# RPi-FabScan-HAT_v11.net
KiCad netlist of a schematic drawn in EAGLE
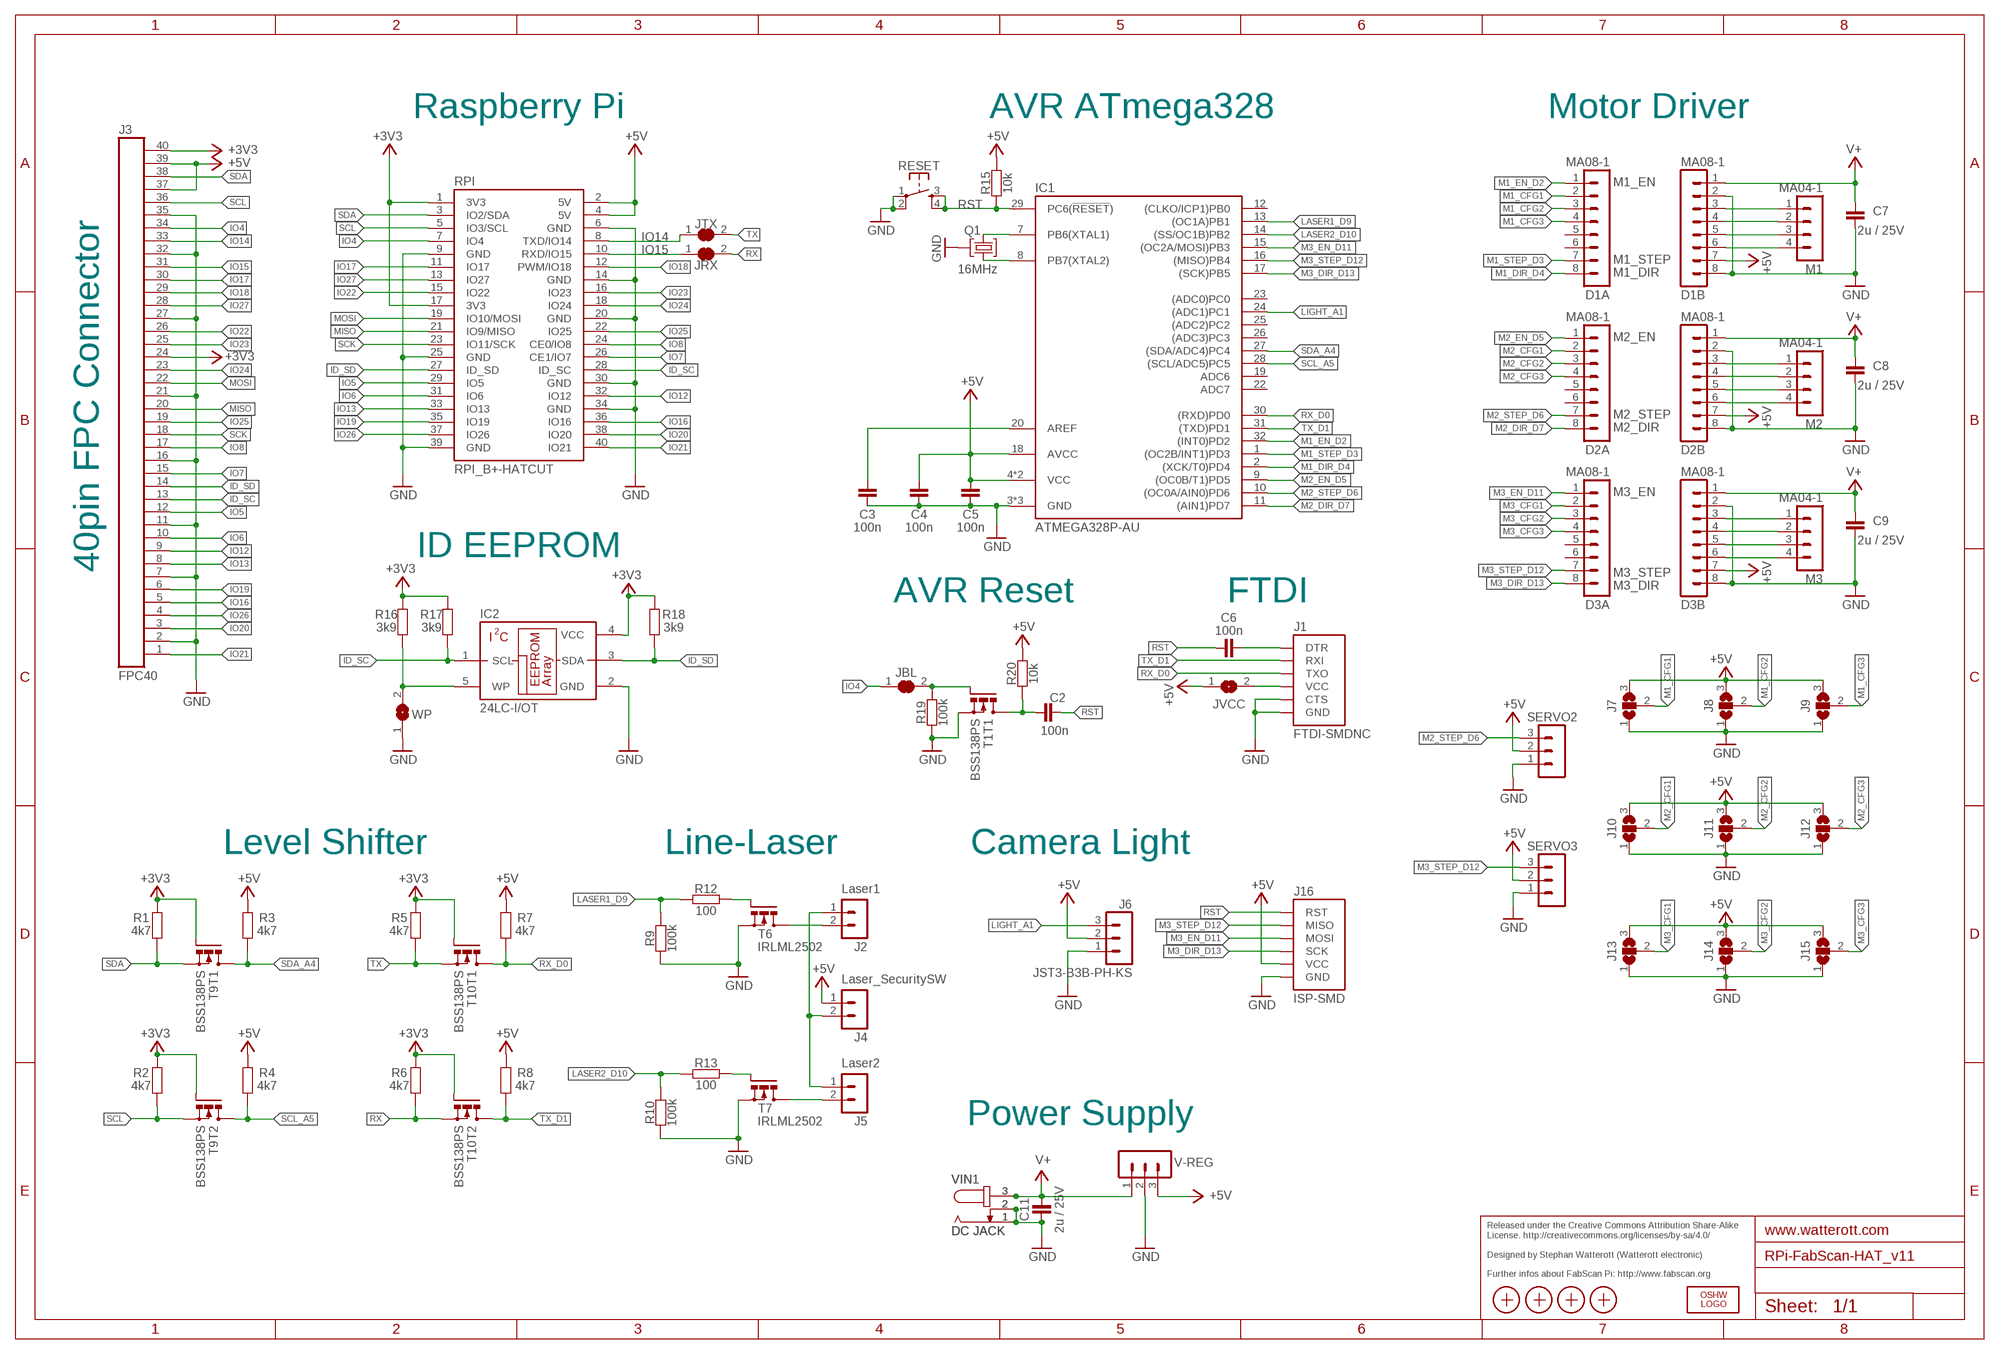
[diagram p0: schematic, sheet 1]

(export (version "E")
  (design (tool "Eeschema 10.0.6"))
  (components
    (comp (ref "1")
      (value "PASSER-07")
      (footprint "eagle-import:PASSER_07MM")
      (libsource (lib "eagle-import") (part "PASSER-07"))
    )
    (comp (ref "2")
      (value "PASSER-07")
      (footprint "eagle-import:PASSER_07MM")
      (libsource (lib "eagle-import") (part "PASSER-07"))
    )
    (comp (ref "C2")
      (value "100n")
      (footprint "eagle-import:C0402")
      (libsource (lib "eagle-import") (part "CAPACITOR-0402"))
    )
    (comp (ref "C3")
      (value "100n")
      (footprint "eagle-import:C0402")
      (libsource (lib "eagle-import") (part "CAPACITOR-0402"))
    )
    (comp (ref "C4")
      (value "100n")
      (footprint "eagle-import:C0402")
      (libsource (lib "eagle-import") (part "CAPACITOR-0402"))
    )
    (comp (ref "C5")
      (value "100n")
      (footprint "eagle-import:C0402")
      (libsource (lib "eagle-import") (part "CAPACITOR-0402"))
    )
    (comp (ref "C6")
      (value "100n")
      (footprint "eagle-import:C0402")
      (libsource (lib "eagle-import") (part "CAPACITOR-0402"))
    )
    (comp (ref "C7")
      (value "2u / 25V")
      (footprint "eagle-import:C1206")
      (libsource (lib "eagle-import") (part "CAPACITOR-1206"))
    )
    (comp (ref "C8")
      (value "2u / 25V")
      (footprint "eagle-import:C1206")
      (libsource (lib "eagle-import") (part "CAPACITOR-1206"))
    )
    (comp (ref "C9")
      (value "2u / 25V")
      (footprint "eagle-import:C1206")
      (libsource (lib "eagle-import") (part "CAPACITOR-1206"))
    )
    (comp (ref "C11")
      (value "2u / 25V")
      (footprint "eagle-import:C1206")
      (libsource (lib "eagle-import") (part "CAPACITOR-1206"))
    )
    (comp (ref "D1A")
      (value "MA08-1")
      (footprint "eagle-import:MA08-1")
      (libsource (lib "eagle-import") (part "MA08-1"))
    )
    (comp (ref "D1B")
      (value "MA08-1")
      (footprint "eagle-import:MA08-1")
      (libsource (lib "eagle-import") (part "MA08-1"))
    )
    (comp (ref "D2A")
      (value "MA08-1")
      (footprint "eagle-import:MA08-1")
      (libsource (lib "eagle-import") (part "MA08-1"))
    )
    (comp (ref "D2B")
      (value "MA08-1")
      (footprint "eagle-import:MA08-1")
      (libsource (lib "eagle-import") (part "MA08-1"))
    )
    (comp (ref "D3A")
      (value "MA08-1")
      (footprint "eagle-import:MA08-1")
      (libsource (lib "eagle-import") (part "MA08-1"))
    )
    (comp (ref "D3B")
      (value "MA08-1")
      (footprint "eagle-import:MA08-1")
      (libsource (lib "eagle-import") (part "MA08-1"))
    )
    (comp (ref "IC1")
      (value "ATMEGA328P-AU")
      (footprint "eagle-import:TQFP32")
      (libsource (lib "eagle-import") (part "ATMEGA328P-AU"))
    )
    (comp (ref "IC2")
      (value "24LC-I/OT")
      (footprint "eagle-import:SOT23-5")
      (libsource (lib "eagle-import") (part "24LC-I/OT"))
    )
    (comp (ref "J1")
      (value "FTDI-SMDNC")
      (footprint "eagle-import:FTDI_SMDNC")
      (libsource (lib "eagle-import") (part "FTDI-SMDNC"))
    )
    (comp (ref "J2")
      (value "Laser1")
      (footprint "eagle-import:MA02-1")
      (libsource (lib "eagle-import") (part "MA02-1"))
    )
    (comp (ref "J3")
      (value "FPC40")
      (footprint "eagle-import:FPC40-0.5")
      (libsource (lib "eagle-import") (part "FPC40"))
    )
    (comp (ref "J4")
      (value "Laser_SecuritySW")
      (footprint "eagle-import:MA02-1")
      (libsource (lib "eagle-import") (part "MA02-1"))
    )
    (comp (ref "J5")
      (value "Laser2")
      (footprint "eagle-import:MA02-1")
      (libsource (lib "eagle-import") (part "MA02-1"))
    )
    (comp (ref "J6")
      (value "JST3-B3B-PH-KS")
      (footprint "eagle-import:JST_B3B-PH-KS")
      (libsource (lib "eagle-import") (part "JST3-B3B-PH-KS"))
    )
    (comp (ref "J7")
      (value "JUMPER3-0603-NC")
      (footprint "eagle-import:JUMPER3-0603_NC")
      (libsource (lib "eagle-import") (part "JUMPER3-0603-NC"))
    )
    (comp (ref "J8")
      (value "JUMPER3-0603-NC")
      (footprint "eagle-import:JUMPER3-0603_NC")
      (libsource (lib "eagle-import") (part "JUMPER3-0603-NC"))
    )
    (comp (ref "J9")
      (value "JUMPER3-0603-NC")
      (footprint "eagle-import:JUMPER3-0603_NC")
      (libsource (lib "eagle-import") (part "JUMPER3-0603-NC"))
    )
    (comp (ref "J10")
      (value "JUMPER3-0603-NC")
      (footprint "eagle-import:JUMPER3-0603_NC")
      (libsource (lib "eagle-import") (part "JUMPER3-0603-NC"))
    )
    (comp (ref "J11")
      (value "JUMPER3-0603-NC")
      (footprint "eagle-import:JUMPER3-0603_NC")
      (libsource (lib "eagle-import") (part "JUMPER3-0603-NC"))
    )
    (comp (ref "J12")
      (value "JUMPER3-0603-NC")
      (footprint "eagle-import:JUMPER3-0603_NC")
      (libsource (lib "eagle-import") (part "JUMPER3-0603-NC"))
    )
    (comp (ref "J13")
      (value "JUMPER3-0603-NC")
      (footprint "eagle-import:JUMPER3-0603_NC")
      (libsource (lib "eagle-import") (part "JUMPER3-0603-NC"))
    )
    (comp (ref "J14")
      (value "JUMPER3-0603-NC")
      (footprint "eagle-import:JUMPER3-0603_NC")
      (libsource (lib "eagle-import") (part "JUMPER3-0603-NC"))
    )
    (comp (ref "J15")
      (value "JUMPER3-0603-NC")
      (footprint "eagle-import:JUMPER3-0603_NC")
      (libsource (lib "eagle-import") (part "JUMPER3-0603-NC"))
    )
    (comp (ref "J16")
      (value "ISP-SMD")
      (footprint "eagle-import:ISP-2X3_SMD")
      (libsource (lib "eagle-import") (part "ISP-SMD"))
    )
    (comp (ref "JBL")
      (value "JUMPER2-0402-NC")
      (footprint "eagle-import:JUMPER2-0402_NC")
      (libsource (lib "eagle-import") (part "JUMPER2-0402-NC"))
    )
    (comp (ref "JRX")
      (value "JUMPER2-0402-NC")
      (footprint "eagle-import:JUMPER2-0402_NC")
      (libsource (lib "eagle-import") (part "JUMPER2-0402-NC"))
    )
    (comp (ref "JTX")
      (value "JUMPER2-0402-NC")
      (footprint "eagle-import:JUMPER2-0402_NC")
      (libsource (lib "eagle-import") (part "JUMPER2-0402-NC"))
    )
    (comp (ref "JVCC")
      (value "JUMPER2-0402-NC")
      (footprint "eagle-import:JUMPER2-0402_NC")
      (libsource (lib "eagle-import") (part "JUMPER2-0402-NC"))
    )
    (comp (ref "LOGO2")
      (value "OSHW_LOGOX0100")
      (footprint "eagle-import:OSHW_6X100")
      (libsource (lib "eagle-import") (part "OSHW_LOGOX0100"))
    )
    (comp (ref "M1")
      (value "MA04-1")
      (footprint "eagle-import:MA04-1")
      (libsource (lib "eagle-import") (part "MA04-1"))
    )
    (comp (ref "M2")
      (value "MA04-1")
      (footprint "eagle-import:MA04-1")
      (libsource (lib "eagle-import") (part "MA04-1"))
    )
    (comp (ref "M3")
      (value "MA04-1")
      (footprint "eagle-import:MA04-1")
      (libsource (lib "eagle-import") (part "MA04-1"))
    )
    (comp (ref "Q1")
      (value "16MHz")
      (footprint "eagle-import:CRYSTAL_32X13")
      (libsource (lib "eagle-import") (part "CRYSTAL-RES-32"))
    )
    (comp (ref "R1")
      (value "4k7")
      (footprint "eagle-import:C0402")
      (libsource (lib "eagle-import") (part "RESISTOR-0402"))
    )
    (comp (ref "R2")
      (value "4k7")
      (footprint "eagle-import:C0402")
      (libsource (lib "eagle-import") (part "RESISTOR-0402"))
    )
    (comp (ref "R3")
      (value "4k7")
      (footprint "eagle-import:C0402")
      (libsource (lib "eagle-import") (part "RESISTOR-0402"))
    )
    (comp (ref "R4")
      (value "4k7")
      (footprint "eagle-import:C0402")
      (libsource (lib "eagle-import") (part "RESISTOR-0402"))
    )
    (comp (ref "R5")
      (value "4k7")
      (footprint "eagle-import:C0402")
      (libsource (lib "eagle-import") (part "RESISTOR-0402"))
    )
    (comp (ref "R6")
      (value "4k7")
      (footprint "eagle-import:C0402")
      (libsource (lib "eagle-import") (part "RESISTOR-0402"))
    )
    (comp (ref "R7")
      (value "4k7")
      (footprint "eagle-import:C0402")
      (libsource (lib "eagle-import") (part "RESISTOR-0402"))
    )
    (comp (ref "R8")
      (value "4k7")
      (footprint "eagle-import:C0402")
      (libsource (lib "eagle-import") (part "RESISTOR-0402"))
    )
    (comp (ref "R9")
      (value "100k")
      (footprint "eagle-import:C0402")
      (libsource (lib "eagle-import") (part "RESISTOR-0402"))
    )
    (comp (ref "R10")
      (value "100k")
      (footprint "eagle-import:C0402")
      (libsource (lib "eagle-import") (part "RESISTOR-0402"))
    )
    (comp (ref "R12")
      (value "100")
      (footprint "eagle-import:C0402")
      (libsource (lib "eagle-import") (part "RESISTOR-0402"))
    )
    (comp (ref "R13")
      (value "100")
      (footprint "eagle-import:C0402")
      (libsource (lib "eagle-import") (part "RESISTOR-0402"))
    )
    (comp (ref "R15")
      (value "10k")
      (footprint "eagle-import:C0402")
      (libsource (lib "eagle-import") (part "RESISTOR-0402"))
    )
    (comp (ref "R16")
      (value "3k9")
      (footprint "eagle-import:C0402")
      (libsource (lib "eagle-import") (part "RESISTOR-0402"))
    )
    (comp (ref "R17")
      (value "3k9")
      (footprint "eagle-import:C0402")
      (libsource (lib "eagle-import") (part "RESISTOR-0402"))
    )
    (comp (ref "R18")
      (value "3k9")
      (footprint "eagle-import:C0402")
      (libsource (lib "eagle-import") (part "RESISTOR-0402"))
    )
    (comp (ref "R19")
      (value "100k")
      (footprint "eagle-import:C0402")
      (libsource (lib "eagle-import") (part "RESISTOR-0402"))
    )
    (comp (ref "R20")
      (value "10k")
      (footprint "eagle-import:C0402")
      (libsource (lib "eagle-import") (part "RESISTOR-0402"))
    )
    (comp (ref "RESET")
      (value "SW-TACTILE-PTS840P")
      (footprint "eagle-import:SW_PTS840P")
      (libsource (lib "eagle-import") (part "SW-TACTILE-PTS840P"))
    )
    (comp (ref "RPI")
      (value "RPI_B+-HATCUT")
      (footprint "eagle-import:RPI-B+HAT_CUTOUT")
      (libsource (lib "eagle-import") (part "RPI_B+-HATCUT"))
    )
    (comp (ref "SERVO2")
      (value "MA03-1")
      (footprint "eagle-import:MA03-1")
      (libsource (lib "eagle-import") (part "MA03-1"))
    )
    (comp (ref "SERVO3")
      (value "MA03-1")
      (footprint "eagle-import:MA03-1")
      (libsource (lib "eagle-import") (part "MA03-1"))
    )
    (comp (ref "T1")
      (value "BSS138PS")
      (footprint "eagle-import:SOT363")
      (libsource (lib "eagle-import") (part "BSS138PS"))
    )
    (comp (ref "T6")
      (value "IRLML2502")
      (footprint "eagle-import:SOT23")
      (libsource (lib "eagle-import") (part "MOSFET-N-SOT23"))
    )
    (comp (ref "T7")
      (value "IRLML2502")
      (footprint "eagle-import:SOT23")
      (libsource (lib "eagle-import") (part "MOSFET-N-SOT23"))
    )
    (comp (ref "T9")
      (value "BSS138PS")
      (footprint "eagle-import:SOT363")
      (libsource (lib "eagle-import") (part "BSS138PS"))
    )
    (comp (ref "T10")
      (value "BSS138PS")
      (footprint "eagle-import:SOT363")
      (libsource (lib "eagle-import") (part "BSS138PS"))
    )
    (comp (ref "V-REG")
      (value "MA03-1")
      (footprint "eagle-import:MA03-1")
      (libsource (lib "eagle-import") (part "MA03-1"))
    )
    (comp (ref "VIN")
      (value "DC JACK")
      (footprint "eagle-import:DC-JACK")
      (libsource (lib "eagle-import") (part "DC-JACK-2.1"))
    )
    (comp (ref "VIN1")
      (value "DC JACK")
      (footprint "eagle-import:DC-JACK")
      (libsource (lib "eagle-import") (part "DC-JACK-2.1"))
    )
    (comp (ref "WP")
      (value "JUMPER2-0402-NC")
      (footprint "eagle-import:JUMPER2-0402_NC")
      (libsource (lib "eagle-import") (part "JUMPER2-0402-NC"))
    )
    (comp (ref "X1")
      (value "PASSER-07")
      (footprint "eagle-import:PASSER_07MM")
      (libsource (lib "eagle-import") (part "PASSER-07"))
    )
    (comp (ref "X4")
      (value "PASSER-07")
      (footprint "eagle-import:PASSER_07MM")
      (libsource (lib "eagle-import") (part "PASSER-07"))
    )
  )
  (nets
    (net (code "1") (name "+3V3") (class "Default")
      (node (ref "IC2") (pin "4") (pinfunction "VCC_4") (pintype "power_in"))
      (node (ref "J3") (pin "24") (pinfunction "24_24") (pintype "passive"))
      (node (ref "J3") (pin "40") (pinfunction "40_40") (pintype "passive"))
      (node (ref "R1") (pin "1") (pinfunction "1_1") (pintype "passive"))
      (node (ref "R16") (pin "2") (pinfunction "2_2") (pintype "passive"))
      (node (ref "R17") (pin "2") (pinfunction "2_2") (pintype "passive"))
      (node (ref "R18") (pin "2") (pinfunction "2_2") (pintype "passive"))
      (node (ref "R2") (pin "1") (pinfunction "1_1") (pintype "passive"))
      (node (ref "R5") (pin "1") (pinfunction "1_1") (pintype "passive"))
      (node (ref "R6") (pin "1") (pinfunction "1_1") (pintype "passive"))
      (node (ref "RPI") (pin "1") (pinfunction "3V3_1") (pintype "passive"))
      (node (ref "RPI") (pin "17") (pinfunction "3V3_17") (pintype "passive"))
      (node (ref "T10") (pin "2") (pinfunction "G_2") (pintype "passive"))
      (node (ref "T10") (pin "5") (pinfunction "G_5") (pintype "passive"))
      (node (ref "T9") (pin "2") (pinfunction "G_2") (pintype "passive"))
      (node (ref "T9") (pin "5") (pinfunction "G_5") (pintype "passive"))
    )
    (net (code "2") (name "+5V") (class "Default")
      (node (ref "C4") (pin "2") (pinfunction "2_2") (pintype "passive"))
      (node (ref "C5") (pin "2") (pinfunction "2_2") (pintype "passive"))
      (node (ref "D1B") (pin "7") (pinfunction "7_7") (pintype "passive"))
      (node (ref "D2B") (pin "7") (pinfunction "7_7") (pintype "passive"))
      (node (ref "D3B") (pin "7") (pinfunction "7_7") (pintype "passive"))
      (node (ref "IC1") (pin "18") (pinfunction "AVCC_18") (pintype "power_in"))
      (node (ref "IC1") (pin "4") (pinfunction "VCC_4") (pintype "power_in"))
      (node (ref "IC1") (pin "6") (pinfunction "VCC_6") (pintype "power_in"))
      (node (ref "J10") (pin "3") (pinfunction "3_3") (pintype "passive"))
      (node (ref "J11") (pin "3") (pinfunction "3_3") (pintype "passive"))
      (node (ref "J12") (pin "3") (pinfunction "3_3") (pintype "passive"))
      (node (ref "J13") (pin "3") (pinfunction "3_3") (pintype "passive"))
      (node (ref "J14") (pin "3") (pinfunction "3_3") (pintype "passive"))
      (node (ref "J15") (pin "3") (pinfunction "3_3") (pintype "passive"))
      (node (ref "J16") (pin "VCC") (pinfunction "VCC_VCC") (pintype "power_in"))
      (node (ref "J3") (pin "37") (pinfunction "37_37") (pintype "passive"))
      (node (ref "J3") (pin "39") (pinfunction "39_39") (pintype "passive"))
      (node (ref "J4") (pin "1") (pinfunction "1_1") (pintype "passive"))
      (node (ref "J6") (pin "2") (pinfunction "2_2") (pintype "passive"))
      (node (ref "J7") (pin "3") (pinfunction "3_3") (pintype "passive"))
      (node (ref "J8") (pin "3") (pinfunction "3_3") (pintype "passive"))
      (node (ref "J9") (pin "3") (pinfunction "3_3") (pintype "passive"))
      (node (ref "JVCC") (pin "1") (pinfunction "1_1") (pintype "passive"))
      (node (ref "R15") (pin "2") (pinfunction "2_2") (pintype "passive"))
      (node (ref "R20") (pin "2") (pinfunction "2_2") (pintype "passive"))
      (node (ref "R3") (pin "1") (pinfunction "1_1") (pintype "passive"))
      (node (ref "R4") (pin "1") (pinfunction "1_1") (pintype "passive"))
      (node (ref "R7") (pin "1") (pinfunction "1_1") (pintype "passive"))
      (node (ref "R8") (pin "1") (pinfunction "1_1") (pintype "passive"))
      (node (ref "RPI") (pin "2") (pinfunction "5V_2") (pintype "passive"))
      (node (ref "RPI") (pin "4") (pinfunction "5V_4") (pintype "passive"))
      (node (ref "SERVO2") (pin "2") (pinfunction "2_2") (pintype "passive"))
      (node (ref "SERVO3") (pin "2") (pinfunction "2_2") (pintype "passive"))
      (node (ref "V-REG") (pin "3") (pinfunction "3_3") (pintype "passive"))
    )
    (net (code "3") (name "GND") (class "Default")
      (node (ref "C11") (pin "1") (pinfunction "1_1") (pintype "passive"))
      (node (ref "C3") (pin "1") (pinfunction "1_1") (pintype "passive"))
      (node (ref "C4") (pin "1") (pinfunction "1_1") (pintype "passive"))
      (node (ref "C5") (pin "1") (pinfunction "1_1") (pintype "passive"))
      (node (ref "C7") (pin "1") (pinfunction "1_1") (pintype "passive"))
      (node (ref "C8") (pin "1") (pinfunction "1_1") (pintype "passive"))
      (node (ref "C9") (pin "1") (pinfunction "1_1") (pintype "passive"))
      (node (ref "D1B") (pin "2") (pinfunction "2_2") (pintype "passive"))
      (node (ref "D1B") (pin "8") (pinfunction "8_8") (pintype "passive"))
      (node (ref "D2B") (pin "2") (pinfunction "2_2") (pintype "passive"))
      (node (ref "D2B") (pin "8") (pinfunction "8_8") (pintype "passive"))
      (node (ref "D3B") (pin "2") (pinfunction "2_2") (pintype "passive"))
      (node (ref "D3B") (pin "8") (pinfunction "8_8") (pintype "passive"))
      (node (ref "IC1") (pin "21") (pinfunction "GND_21") (pintype "power_in"))
      (node (ref "IC1") (pin "3") (pinfunction "GND_3") (pintype "power_in"))
      (node (ref "IC1") (pin "5") (pinfunction "GND_5") (pintype "power_in"))
      (node (ref "IC2") (pin "2") (pinfunction "GND_2") (pintype "power_in"))
      (node (ref "J1") (pin "1-GND") (pinfunction "GND_1-GND") (pintype "power_in"))
      (node (ref "J1") (pin "2-CTS") (pinfunction "CTS_2-CTS") (pintype "bidirectional"))
      (node (ref "J10") (pin "1") (pinfunction "1_1") (pintype "passive"))
      (node (ref "J11") (pin "1") (pinfunction "1_1") (pintype "passive"))
      (node (ref "J12") (pin "1") (pinfunction "1_1") (pintype "passive"))
      (node (ref "J13") (pin "1") (pinfunction "1_1") (pintype "passive"))
      (node (ref "J14") (pin "1") (pinfunction "1_1") (pintype "passive"))
      (node (ref "J15") (pin "1") (pinfunction "1_1") (pintype "passive"))
      (node (ref "J16") (pin "GND") (pinfunction "GND_GND") (pintype "power_in"))
      (node (ref "J3") (pin "11") (pinfunction "11_11") (pintype "passive"))
      (node (ref "J3") (pin "16") (pinfunction "16_16") (pintype "passive"))
      (node (ref "J3") (pin "2") (pinfunction "2_2") (pintype "passive"))
      (node (ref "J3") (pin "21") (pinfunction "21_21") (pintype "passive"))
      (node (ref "J3") (pin "27") (pinfunction "27_27") (pintype "passive"))
      (node (ref "J3") (pin "32") (pinfunction "32_32") (pintype "passive"))
      (node (ref "J3") (pin "35") (pinfunction "35_35") (pintype "passive"))
      (node (ref "J3") (pin "7") (pinfunction "7_7") (pintype "passive"))
      (node (ref "J6") (pin "1") (pinfunction "1_1") (pintype "passive"))
      (node (ref "J7") (pin "1") (pinfunction "1_1") (pintype "passive"))
      (node (ref "J8") (pin "1") (pinfunction "1_1") (pintype "passive"))
      (node (ref "J9") (pin "1") (pinfunction "1_1") (pintype "passive"))
      (node (ref "Q1") (pin "GND") (pinfunction "GND_GND") (pintype "passive"))
      (node (ref "R10") (pin "1") (pinfunction "1_1") (pintype "passive"))
      (node (ref "R19") (pin "1") (pinfunction "1_1") (pintype "passive"))
      (node (ref "R9") (pin "1") (pinfunction "1_1") (pintype "passive"))
      (node (ref "RESET") (pin "1") (pinfunction "P1_1") (pintype "passive"))
      (node (ref "RESET") (pin "2") (pinfunction "P2_2") (pintype "passive"))
      (node (ref "RPI") (pin "14") (pinfunction "GND_14") (pintype "passive"))
      (node (ref "RPI") (pin "20") (pinfunction "GND_20") (pintype "passive"))
      (node (ref "RPI") (pin "25") (pinfunction "GND_25") (pintype "passive"))
      (node (ref "RPI") (pin "30") (pinfunction "GND_30") (pintype "bidirectional"))
      (node (ref "RPI") (pin "34") (pinfunction "GND_34") (pintype "bidirectional"))
      (node (ref "RPI") (pin "39") (pinfunction "GND_39") (pintype "bidirectional"))
      (node (ref "RPI") (pin "6") (pinfunction "GND_6") (pintype "passive"))
      (node (ref "RPI") (pin "9") (pinfunction "GND_9") (pintype "passive"))
      (node (ref "SERVO2") (pin "1") (pinfunction "1_1") (pintype "passive"))
      (node (ref "SERVO3") (pin "1") (pinfunction "1_1") (pintype "passive"))
      (node (ref "T1") (pin "1") (pinfunction "S_1") (pintype "passive"))
      (node (ref "T6") (pin "2") (pinfunction "S_2") (pintype "passive"))
      (node (ref "T7") (pin "2") (pinfunction "S_2") (pintype "passive"))
      (node (ref "V-REG") (pin "2") (pinfunction "2_2") (pintype "passive"))
      (node (ref "VIN") (pin "1") (pinfunction "1_1") (pintype "passive"))
      (node (ref "VIN") (pin "2") (pinfunction "2_2") (pintype "passive"))
      (node (ref "VIN1") (pin "1") (pinfunction "1_1") (pintype "passive"))
      (node (ref "VIN1") (pin "2") (pinfunction "2_2") (pintype "passive"))
      (node (ref "WP") (pin "1") (pinfunction "1_1") (pintype "passive"))
    )
    (net (code "4") (name "ID_SC") (class "Default")
      (node (ref "IC2") (pin "1") (pinfunction "SCL_1") (pintype "bidirectional"))
      (node (ref "J3") (pin "13") (pinfunction "13_13") (pintype "passive"))
      (node (ref "R17") (pin "1") (pinfunction "1_1") (pintype "passive"))
      (node (ref "RPI") (pin "28") (pinfunction "ID_SC_28") (pintype "bidirectional"))
    )
    (net (code "5") (name "ID_SD") (class "Default")
      (node (ref "IC2") (pin "3") (pinfunction "SDA_3") (pintype "bidirectional"))
      (node (ref "J3") (pin "14") (pinfunction "14_14") (pintype "passive"))
      (node (ref "R18") (pin "1") (pinfunction "1_1") (pintype "passive"))
      (node (ref "RPI") (pin "27") (pinfunction "ID_SD_27") (pintype "bidirectional"))
    )
    (net (code "6") (name "IO4") (class "Default")
      (node (ref "J3") (pin "34") (pinfunction "34_34") (pintype "passive"))
      (node (ref "JBL") (pin "1") (pinfunction "1_1") (pintype "passive"))
      (node (ref "RPI") (pin "7") (pinfunction "IO4_7") (pintype "passive"))
    )
    (net (code "7") (name "IO5") (class "Default")
      (node (ref "J3") (pin "12") (pinfunction "12_12") (pintype "passive"))
      (node (ref "RPI") (pin "29") (pinfunction "IO5_29") (pintype "bidirectional"))
    )
    (net (code "8") (name "IO6") (class "Default")
      (node (ref "J3") (pin "10") (pinfunction "10_10") (pintype "passive"))
      (node (ref "RPI") (pin "31") (pinfunction "IO6_31") (pintype "bidirectional"))
    )
    (net (code "9") (name "IO7") (class "Default")
      (node (ref "J3") (pin "15") (pinfunction "15_15") (pintype "passive"))
      (node (ref "RPI") (pin "26") (pinfunction "CE1/IO7_26") (pintype "passive"))
    )
    (net (code "10") (name "IO8") (class "Default")
      (node (ref "J3") (pin "17") (pinfunction "17_17") (pintype "passive"))
      (node (ref "RPI") (pin "24") (pinfunction "CE0/IO8_24") (pintype "passive"))
    )
    (net (code "11") (name "IO12") (class "Default")
      (node (ref "J3") (pin "9") (pinfunction "9_9") (pintype "passive"))
      (node (ref "RPI") (pin "32") (pinfunction "IO12_32") (pintype "bidirectional"))
    )
    (net (code "12") (name "IO13") (class "Default")
      (node (ref "J3") (pin "8") (pinfunction "8_8") (pintype "passive"))
      (node (ref "RPI") (pin "33") (pinfunction "IO13_33") (pintype "bidirectional"))
    )
    (net (code "13") (name "IO14") (class "Default")
      (node (ref "J3") (pin "33") (pinfunction "33_33") (pintype "passive"))
      (node (ref "JTX") (pin "1") (pinfunction "1_1") (pintype "passive"))
      (node (ref "RPI") (pin "8") (pinfunction "TXD/IO14_8") (pintype "passive"))
    )
    (net (code "14") (name "IO15") (class "Default")
      (node (ref "J3") (pin "31") (pinfunction "31_31") (pintype "passive"))
      (node (ref "JRX") (pin "1") (pinfunction "1_1") (pintype "passive"))
      (node (ref "RPI") (pin "10") (pinfunction "RXD/IO15_10") (pintype "passive"))
    )
    (net (code "15") (name "IO16") (class "Default")
      (node (ref "J3") (pin "5") (pinfunction "5_5") (pintype "passive"))
      (node (ref "RPI") (pin "36") (pinfunction "IO16_36") (pintype "bidirectional"))
    )
    (net (code "16") (name "IO17") (class "Default")
      (node (ref "J3") (pin "30") (pinfunction "30_30") (pintype "passive"))
      (node (ref "RPI") (pin "11") (pinfunction "IO17_11") (pintype "passive"))
    )
    (net (code "17") (name "IO18") (class "Default")
      (node (ref "J3") (pin "29") (pinfunction "29_29") (pintype "passive"))
      (node (ref "RPI") (pin "12") (pinfunction "PWM/IO18_12") (pintype "passive"))
    )
    (net (code "18") (name "IO19") (class "Default")
      (node (ref "J3") (pin "6") (pinfunction "6_6") (pintype "passive"))
      (node (ref "RPI") (pin "35") (pinfunction "IO19_35") (pintype "bidirectional"))
    )
    (net (code "19") (name "IO20") (class "Default")
      (node (ref "J3") (pin "3") (pinfunction "3_3") (pintype "passive"))
      (node (ref "RPI") (pin "38") (pinfunction "IO20_38") (pintype "bidirectional"))
    )
    (net (code "20") (name "IO21") (class "Default")
      (node (ref "J3") (pin "1") (pinfunction "1_1") (pintype "passive"))
      (node (ref "RPI") (pin "40") (pinfunction "IO21_40") (pintype "bidirectional"))
    )
    (net (code "21") (name "IO22") (class "Default")
      (node (ref "J3") (pin "26") (pinfunction "26_26") (pintype "passive"))
      (node (ref "RPI") (pin "15") (pinfunction "IO22_15") (pintype "passive"))
    )
    (net (code "22") (name "IO23") (class "Default")
      (node (ref "J3") (pin "25") (pinfunction "25_25") (pintype "passive"))
      (node (ref "RPI") (pin "16") (pinfunction "IO23_16") (pintype "passive"))
    )
    (net (code "23") (name "IO24") (class "Default")
      (node (ref "J3") (pin "23") (pinfunction "23_23") (pintype "passive"))
      (node (ref "RPI") (pin "18") (pinfunction "IO24_18") (pintype "passive"))
    )
    (net (code "24") (name "IO25") (class "Default")
      (node (ref "J3") (pin "19") (pinfunction "19_19") (pintype "passive"))
      (node (ref "RPI") (pin "22") (pinfunction "IO25_22") (pintype "passive"))
    )
    (net (code "25") (name "IO26") (class "Default")
      (node (ref "J3") (pin "4") (pinfunction "4_4") (pintype "passive"))
      (node (ref "RPI") (pin "37") (pinfunction "IO26_37") (pintype "bidirectional"))
    )
    (net (code "26") (name "IO27") (class "Default")
      (node (ref "J3") (pin "28") (pinfunction "28_28") (pintype "passive"))
      (node (ref "RPI") (pin "13") (pinfunction "IO27_13") (pintype "passive"))
    )
    (net (code "27") (name "LASER1_D9") (class "Default")
      (node (ref "IC1") (pin "13") (pinfunction "(OC1A)PB1_13") (pintype "bidirectional"))
      (node (ref "R12") (pin "1") (pinfunction "1_1") (pintype "passive"))
      (node (ref "R9") (pin "2") (pinfunction "2_2") (pintype "passive"))
    )
    (net (code "28") (name "LASER2_D10") (class "Default")
      (node (ref "IC1") (pin "14") (pinfunction "(SS/OC1B)PB2_14") (pintype "bidirectional"))
      (node (ref "R10") (pin "2") (pinfunction "2_2") (pintype "passive"))
      (node (ref "R13") (pin "1") (pinfunction "1_1") (pintype "passive"))
    )
    (net (code "29") (name "LIGHT_A1") (class "Default")
      (node (ref "IC1") (pin "24") (pinfunction "(ADC1)PC1_24") (pintype "bidirectional"))
      (node (ref "J6") (pin "3") (pinfunction "3_3") (pintype "passive"))
    )
    (net (code "30") (name "M1_CFG1") (class "Default")
      (node (ref "D1A") (pin "2") (pinfunction "2_2") (pintype "passive"))
      (node (ref "J7") (pin "2") (pinfunction "2_2") (pintype "passive"))
    )
    (net (code "31") (name "M1_CFG2") (class "Default")
      (node (ref "D1A") (pin "3") (pinfunction "3_3") (pintype "passive"))
      (node (ref "J8") (pin "2") (pinfunction "2_2") (pintype "passive"))
    )
    (net (code "32") (name "M1_CFG3") (class "Default")
      (node (ref "D1A") (pin "4") (pinfunction "4_4") (pintype "passive"))
      (node (ref "J9") (pin "2") (pinfunction "2_2") (pintype "passive"))
    )
    (net (code "33") (name "M1_DIR_D4") (class "Default")
      (node (ref "D1A") (pin "8") (pinfunction "8_8") (pintype "passive"))
      (node (ref "IC1") (pin "2") (pinfunction "(XCK/T0)PD4_2") (pintype "bidirectional"))
    )
    (net (code "34") (name "M1_EN_D2") (class "Default")
      (node (ref "D1A") (pin "1") (pinfunction "1_1") (pintype "passive"))
      (node (ref "IC1") (pin "32") (pinfunction "(INT0)PD2_32") (pintype "bidirectional"))
    )
    (net (code "35") (name "M1_STEP_D3") (class "Default")
      (node (ref "D1A") (pin "7") (pinfunction "7_7") (pintype "passive"))
      (node (ref "IC1") (pin "1") (pinfunction "(OC2B/INT1)PD3_1") (pintype "bidirectional"))
    )
    (net (code "36") (name "M2_CFG1") (class "Default")
      (node (ref "D2A") (pin "2") (pinfunction "2_2") (pintype "passive"))
      (node (ref "J10") (pin "2") (pinfunction "2_2") (pintype "passive"))
    )
    (net (code "37") (name "M2_CFG2") (class "Default")
      (node (ref "D2A") (pin "3") (pinfunction "3_3") (pintype "passive"))
      (node (ref "J11") (pin "2") (pinfunction "2_2") (pintype "passive"))
    )
    (net (code "38") (name "M2_CFG3") (class "Default")
      (node (ref "D2A") (pin "4") (pinfunction "4_4") (pintype "passive"))
      (node (ref "J12") (pin "2") (pinfunction "2_2") (pintype "passive"))
    )
    (net (code "39") (name "M2_DIR_D7") (class "Default")
      (node (ref "D2A") (pin "8") (pinfunction "8_8") (pintype "passive"))
      (node (ref "IC1") (pin "11") (pinfunction "(AIN1)PD7_11") (pintype "bidirectional"))
    )
    (net (code "40") (name "M2_EN_D5") (class "Default")
      (node (ref "D2A") (pin "1") (pinfunction "1_1") (pintype "passive"))
      (node (ref "IC1") (pin "9") (pinfunction "(OC0B/T1)PD5_9") (pintype "bidirectional"))
    )
    (net (code "41") (name "M2_STEP_D6") (class "Default")
      (node (ref "D2A") (pin "7") (pinfunction "7_7") (pintype "passive"))
      (node (ref "IC1") (pin "10") (pinfunction "(OC0A/AIN0)PD6_10") (pintype "bidirectional"))
      (node (ref "SERVO2") (pin "3") (pinfunction "3_3") (pintype "passive"))
    )
    (net (code "42") (name "M3_CFG1") (class "Default")
      (node (ref "D3A") (pin "2") (pinfunction "2_2") (pintype "passive"))
      (node (ref "J13") (pin "2") (pinfunction "2_2") (pintype "passive"))
    )
    (net (code "43") (name "M3_CFG2") (class "Default")
      (node (ref "D3A") (pin "3") (pinfunction "3_3") (pintype "passive"))
      (node (ref "J14") (pin "2") (pinfunction "2_2") (pintype "passive"))
    )
    (net (code "44") (name "M3_CFG3") (class "Default")
      (node (ref "D3A") (pin "4") (pinfunction "4_4") (pintype "passive"))
      (node (ref "J15") (pin "2") (pinfunction "2_2") (pintype "passive"))
    )
    (net (code "45") (name "M3_DIR_D13") (class "Default")
      (node (ref "D3A") (pin "8") (pinfunction "8_8") (pintype "passive"))
      (node (ref "IC1") (pin "17") (pinfunction "(SCK)PB5_17") (pintype "bidirectional"))
      (node (ref "J16") (pin "SCK") (pinfunction "SCK_SCK") (pintype "bidirectional"))
    )
    (net (code "46") (name "M3_EN_D11") (class "Default")
      (node (ref "D3A") (pin "1") (pinfunction "1_1") (pintype "passive"))
      (node (ref "IC1") (pin "15") (pinfunction "(OC2A/MOSI)PB3_15") (pintype "bidirectional"))
      (node (ref "J16") (pin "MOSI") (pinfunction "MOSI_MOSI") (pintype "bidirectional"))
    )
    (net (code "47") (name "M3_STEP_D12") (class "Default")
      (node (ref "D3A") (pin "7") (pinfunction "7_7") (pintype "passive"))
      (node (ref "IC1") (pin "16") (pinfunction "(MISO)PB4_16") (pintype "bidirectional"))
      (node (ref "J16") (pin "MISO") (pinfunction "MISO_MISO") (pintype "bidirectional"))
      (node (ref "SERVO3") (pin "3") (pinfunction "3_3") (pintype "passive"))
    )
    (net (code "48") (name "MISO") (class "Default")
      (node (ref "J3") (pin "20") (pinfunction "20_20") (pintype "passive"))
      (node (ref "RPI") (pin "21") (pinfunction "IO9/MISO_21") (pintype "passive"))
    )
    (net (code "49") (name "MOSI") (class "Default")
      (node (ref "J3") (pin "22") (pinfunction "22_22") (pintype "passive"))
      (node (ref "RPI") (pin "19") (pinfunction "IO10/MOSI_19") (pintype "passive"))
    )
    (net (code "50") (name "Net-(D1B-Pad3)") (class "Default")
      (node (ref "D1B") (pin "3") (pinfunction "3_3") (pintype "passive"))
      (node (ref "M1") (pin "1") (pinfunction "1_1") (pintype "passive"))
    )
    (net (code "51") (name "Net-(D1B-Pad4)") (class "Default")
      (node (ref "D1B") (pin "4") (pinfunction "4_4") (pintype "passive"))
      (node (ref "M1") (pin "2") (pinfunction "2_2") (pintype "passive"))
    )
    (net (code "52") (name "Net-(D1B-Pad5)") (class "Default")
      (node (ref "D1B") (pin "5") (pinfunction "5_5") (pintype "passive"))
      (node (ref "M1") (pin "3") (pinfunction "3_3") (pintype "passive"))
    )
    (net (code "53") (name "Net-(D1B-Pad6)") (class "Default")
      (node (ref "D1B") (pin "6") (pinfunction "6_6") (pintype "passive"))
      (node (ref "M1") (pin "4") (pinfunction "4_4") (pintype "passive"))
    )
    (net (code "54") (name "Net-(D2B-Pad3)") (class "Default")
      (node (ref "D2B") (pin "3") (pinfunction "3_3") (pintype "passive"))
      (node (ref "M2") (pin "1") (pinfunction "1_1") (pintype "passive"))
    )
    (net (code "55") (name "Net-(D2B-Pad4)") (class "Default")
      (node (ref "D2B") (pin "4") (pinfunction "4_4") (pintype "passive"))
      (node (ref "M2") (pin "2") (pinfunction "2_2") (pintype "passive"))
    )
    (net (code "56") (name "Net-(D2B-Pad5)") (class "Default")
      (node (ref "D2B") (pin "5") (pinfunction "5_5") (pintype "passive"))
      (node (ref "M2") (pin "3") (pinfunction "3_3") (pintype "passive"))
    )
    (net (code "57") (name "Net-(D2B-Pad6)") (class "Default")
      (node (ref "D2B") (pin "6") (pinfunction "6_6") (pintype "passive"))
      (node (ref "M2") (pin "4") (pinfunction "4_4") (pintype "passive"))
    )
    (net (code "58") (name "Net-(D3B-Pad3)") (class "Default")
      (node (ref "D3B") (pin "3") (pinfunction "3_3") (pintype "passive"))
      (node (ref "M3") (pin "1") (pinfunction "1_1") (pintype "passive"))
    )
    (net (code "59") (name "Net-(D3B-Pad4)") (class "Default")
      (node (ref "D3B") (pin "4") (pinfunction "4_4") (pintype "passive"))
      (node (ref "M3") (pin "2") (pinfunction "2_2") (pintype "passive"))
    )
    (net (code "60") (name "Net-(D3B-Pad5)") (class "Default")
      (node (ref "D3B") (pin "5") (pinfunction "5_5") (pintype "passive"))
      (node (ref "M3") (pin "3") (pinfunction "3_3") (pintype "passive"))
    )
    (net (code "61") (name "Net-(D3B-Pad6)") (class "Default")
      (node (ref "D3B") (pin "6") (pinfunction "6_6") (pintype "passive"))
      (node (ref "M3") (pin "4") (pinfunction "4_4") (pintype "passive"))
    )
    (net (code "62") (name "Net-(IC1-AREF)") (class "Default")
      (node (ref "C3") (pin "2") (pinfunction "2_2") (pintype "passive"))
      (node (ref "IC1") (pin "20") (pinfunction "AREF_20") (pintype "passive"))
    )
    (net (code "63") (name "Net-(IC1-PB6(XTAL1))") (class "Default")
      (node (ref "IC1") (pin "7") (pinfunction "PB6(XTAL1)_7") (pintype "bidirectional"))
      (node (ref "Q1") (pin "2") (pinfunction "2_2") (pintype "passive"))
    )
    (net (code "64") (name "Net-(IC1-PB7(XTAL2))") (class "Default")
      (node (ref "IC1") (pin "8") (pinfunction "PB7(XTAL2)_8") (pintype "bidirectional"))
      (node (ref "Q1") (pin "1") (pinfunction "1_1") (pintype "passive"))
    )
    (net (code "65") (name "Net-(IC2-WP)") (class "Default")
      (node (ref "IC2") (pin "5") (pinfunction "WP_5") (pintype "bidirectional"))
      (node (ref "R16") (pin "1") (pinfunction "1_1") (pintype "passive"))
      (node (ref "WP") (pin "2") (pinfunction "2_2") (pintype "passive"))
    )
    (net (code "66") (name "Net-(J1-DTR)") (class "Default")
      (node (ref "C6") (pin "1") (pinfunction "1_1") (pintype "passive"))
      (node (ref "J1") (pin "6-DTR") (pinfunction "DTR_6-DTR") (pintype "bidirectional"))
    )
    (net (code "67") (name "Net-(J1-VCC)") (class "Default")
      (node (ref "J1") (pin "3-VCC") (pinfunction "VCC_3-VCC") (pintype "power_in"))
      (node (ref "JVCC") (pin "2") (pinfunction "2_2") (pintype "passive"))
    )
    (net (code "68") (name "Net-(J2-Pad1)") (class "Default")
      (node (ref "J2") (pin "1") (pinfunction "1_1") (pintype "passive"))
      (node (ref "J4") (pin "2") (pinfunction "2_2") (pintype "passive"))
      (node (ref "J5") (pin "1") (pinfunction "1_1") (pintype "passive"))
    )
    (net (code "69") (name "Net-(T1A-D)") (class "Default")
      (node (ref "C2") (pin "2") (pinfunction "2_2") (pintype "passive"))
      (node (ref "R20") (pin "1") (pinfunction "1_1") (pintype "passive"))
      (node (ref "T1") (pin "6") (pinfunction "D_6") (pintype "passive"))
    )
    (net (code "70") (name "Net-(T1A-G)") (class "Default")
      (node (ref "JBL") (pin "2") (pinfunction "2_2") (pintype "passive"))
      (node (ref "R19") (pin "2") (pinfunction "2_2") (pintype "passive"))
      (node (ref "T1") (pin "2") (pinfunction "G_2") (pintype "passive"))
    )
    (net (code "71") (name "Net-(T6-D)") (class "Default")
      (node (ref "J2") (pin "2") (pinfunction "2_2") (pintype "passive"))
      (node (ref "T6") (pin "3") (pinfunction "D_3") (pintype "passive"))
    )
    (net (code "72") (name "Net-(T6-G)") (class "Default")
      (node (ref "R12") (pin "2") (pinfunction "2_2") (pintype "passive"))
      (node (ref "T6") (pin "1") (pinfunction "G_1") (pintype "passive"))
    )
    (net (code "73") (name "Net-(T7-D)") (class "Default")
      (node (ref "J5") (pin "2") (pinfunction "2_2") (pintype "passive"))
      (node (ref "T7") (pin "3") (pinfunction "D_3") (pintype "passive"))
    )
    (net (code "74") (name "Net-(T7-G)") (class "Default")
      (node (ref "R13") (pin "2") (pinfunction "2_2") (pintype "passive"))
      (node (ref "T7") (pin "1") (pinfunction "G_1") (pintype "passive"))
    )
    (net (code "75") (name "RST") (class "Default")
      (node (ref "C2") (pin "1") (pinfunction "1_1") (pintype "passive"))
      (node (ref "C6") (pin "2") (pinfunction "2_2") (pintype "passive"))
      (node (ref "IC1") (pin "29") (pinfunction "PC6(~{RESET})_29") (pintype "bidirectional"))
      (node (ref "J16") (pin "RST") (pinfunction "RST_RST") (pintype "bidirectional"))
      (node (ref "R15") (pin "1") (pinfunction "1_1") (pintype "passive"))
      (node (ref "RESET") (pin "3") (pinfunction "S1_3") (pintype "passive"))
      (node (ref "RESET") (pin "4") (pinfunction "S2_4") (pintype "passive"))
    )
    (net (code "76") (name "RX") (class "Default")
      (node (ref "JRX") (pin "2") (pinfunction "2_2") (pintype "passive"))
      (node (ref "R6") (pin "2") (pinfunction "2_2") (pintype "passive"))
      (node (ref "T10") (pin "4") (pinfunction "S_4") (pintype "passive"))
    )
    (net (code "77") (name "RX_D0") (class "Default")
      (node (ref "IC1") (pin "30") (pinfunction "(RXD)PD0_30") (pintype "bidirectional"))
      (node (ref "J1") (pin "4-TXO") (pinfunction "TXO_4-TXO") (pintype "bidirectional"))
      (node (ref "R7") (pin "2") (pinfunction "2_2") (pintype "passive"))
      (node (ref "T10") (pin "6") (pinfunction "D_6") (pintype "passive"))
    )
    (net (code "78") (name "SCK") (class "Default")
      (node (ref "J3") (pin "18") (pinfunction "18_18") (pintype "passive"))
      (node (ref "RPI") (pin "23") (pinfunction "IO11/SCK_23") (pintype "passive"))
    )
    (net (code "79") (name "SCL") (class "Default")
      (node (ref "J3") (pin "36") (pinfunction "36_36") (pintype "passive"))
      (node (ref "R2") (pin "2") (pinfunction "2_2") (pintype "passive"))
      (node (ref "RPI") (pin "5") (pinfunction "IO3/SCL_5") (pintype "passive"))
      (node (ref "T9") (pin "4") (pinfunction "S_4") (pintype "passive"))
    )
    (net (code "80") (name "SCL_A5") (class "Default")
      (node (ref "IC1") (pin "28") (pinfunction "(SCL/ADC5)PC5_28") (pintype "bidirectional"))
      (node (ref "R4") (pin "2") (pinfunction "2_2") (pintype "passive"))
      (node (ref "T9") (pin "3") (pinfunction "D_3") (pintype "passive"))
    )
    (net (code "81") (name "SDA") (class "Default")
      (node (ref "J3") (pin "38") (pinfunction "38_38") (pintype "passive"))
      (node (ref "R1") (pin "2") (pinfunction "2_2") (pintype "passive"))
      (node (ref "RPI") (pin "3") (pinfunction "IO2/SDA_3") (pintype "passive"))
      (node (ref "T9") (pin "1") (pinfunction "S_1") (pintype "passive"))
    )
    (net (code "82") (name "SDA_A4") (class "Default")
      (node (ref "IC1") (pin "27") (pinfunction "(SDA/ADC4)PC4_27") (pintype "bidirectional"))
      (node (ref "R3") (pin "2") (pinfunction "2_2") (pintype "passive"))
      (node (ref "T9") (pin "6") (pinfunction "D_6") (pintype "passive"))
    )
    (net (code "83") (name "TX") (class "Default")
      (node (ref "JTX") (pin "2") (pinfunction "2_2") (pintype "passive"))
      (node (ref "R5") (pin "2") (pinfunction "2_2") (pintype "passive"))
      (node (ref "T10") (pin "1") (pinfunction "S_1") (pintype "passive"))
    )
    (net (code "84") (name "TX_D1") (class "Default")
      (node (ref "IC1") (pin "31") (pinfunction "(TXD)PD1_31") (pintype "bidirectional"))
      (node (ref "J1") (pin "5-RXI") (pinfunction "RXI_5-RXI") (pintype "bidirectional"))
      (node (ref "R8") (pin "2") (pinfunction "2_2") (pintype "passive"))
      (node (ref "T10") (pin "3") (pinfunction "D_3") (pintype "passive"))
    )
    (net (code "85") (name "V+") (class "Default")
      (node (ref "C11") (pin "2") (pinfunction "2_2") (pintype "passive"))
      (node (ref "C7") (pin "2") (pinfunction "2_2") (pintype "passive"))
      (node (ref "C8") (pin "2") (pinfunction "2_2") (pintype "passive"))
      (node (ref "C9") (pin "2") (pinfunction "2_2") (pintype "passive"))
      (node (ref "D1B") (pin "1") (pinfunction "1_1") (pintype "passive"))
      (node (ref "D2B") (pin "1") (pinfunction "1_1") (pintype "passive"))
      (node (ref "D3B") (pin "1") (pinfunction "1_1") (pintype "passive"))
      (node (ref "V-REG") (pin "1") (pinfunction "1_1") (pintype "passive"))
      (node (ref "VIN") (pin "3") (pinfunction "3_3") (pintype "passive"))
      (node (ref "VIN1") (pin "3") (pinfunction "3_3") (pintype "passive"))
    )
    (net (code "86") (name "unconnected-(D1A-Pad5)") (class "Default")
      (node (ref "D1A") (pin "5") (pinfunction "5_5") (pintype "passive"))
    )
    (net (code "87") (name "unconnected-(D1A-Pad6)") (class "Default")
      (node (ref "D1A") (pin "6") (pinfunction "6_6") (pintype "passive"))
    )
    (net (code "88") (name "unconnected-(D2A-Pad5)") (class "Default")
      (node (ref "D2A") (pin "5") (pinfunction "5_5") (pintype "passive"))
    )
    (net (code "89") (name "unconnected-(D2A-Pad6)") (class "Default")
      (node (ref "D2A") (pin "6") (pinfunction "6_6") (pintype "passive"))
    )
    (net (code "90") (name "unconnected-(D3A-Pad5)") (class "Default")
      (node (ref "D3A") (pin "5") (pinfunction "5_5") (pintype "passive"))
    )
    (net (code "91") (name "unconnected-(D3A-Pad6)") (class "Default")
      (node (ref "D3A") (pin "6") (pinfunction "6_6") (pintype "passive"))
    )
    (net (code "92") (name "unconnected-(IC1-(ADC0)PC0-Pad23)") (class "Default")
      (node (ref "IC1") (pin "23") (pinfunction "(ADC0)PC0_23") (pintype "bidirectional"))
    )
    (net (code "93") (name "unconnected-(IC1-(ADC2)PC2-Pad25)") (class "Default")
      (node (ref "IC1") (pin "25") (pinfunction "(ADC2)PC2_25") (pintype "bidirectional"))
    )
    (net (code "94") (name "unconnected-(IC1-(ADC3)PC3-Pad26)") (class "Default")
      (node (ref "IC1") (pin "26") (pinfunction "(ADC3)PC3_26") (pintype "bidirectional"))
    )
    (net (code "95") (name "unconnected-(IC1-(CLKO{slash}ICP1)PB0-Pad12)") (class "Default")
      (node (ref "IC1") (pin "12") (pinfunction "(CLKO/ICP1)PB0_12") (pintype "bidirectional"))
    )
    (net (code "96") (name "unconnected-(IC1-ADC6-Pad19)") (class "Default")
      (node (ref "IC1") (pin "19") (pinfunction "ADC6_19") (pintype "bidirectional"))
    )
    (net (code "97") (name "unconnected-(IC1-ADC7-Pad22)") (class "Default")
      (node (ref "IC1") (pin "22") (pinfunction "ADC7_22") (pintype "bidirectional"))
    )
  )
)
